# UWB_Project.net
KiCad netlist of a schematic drawn in Altium Designer
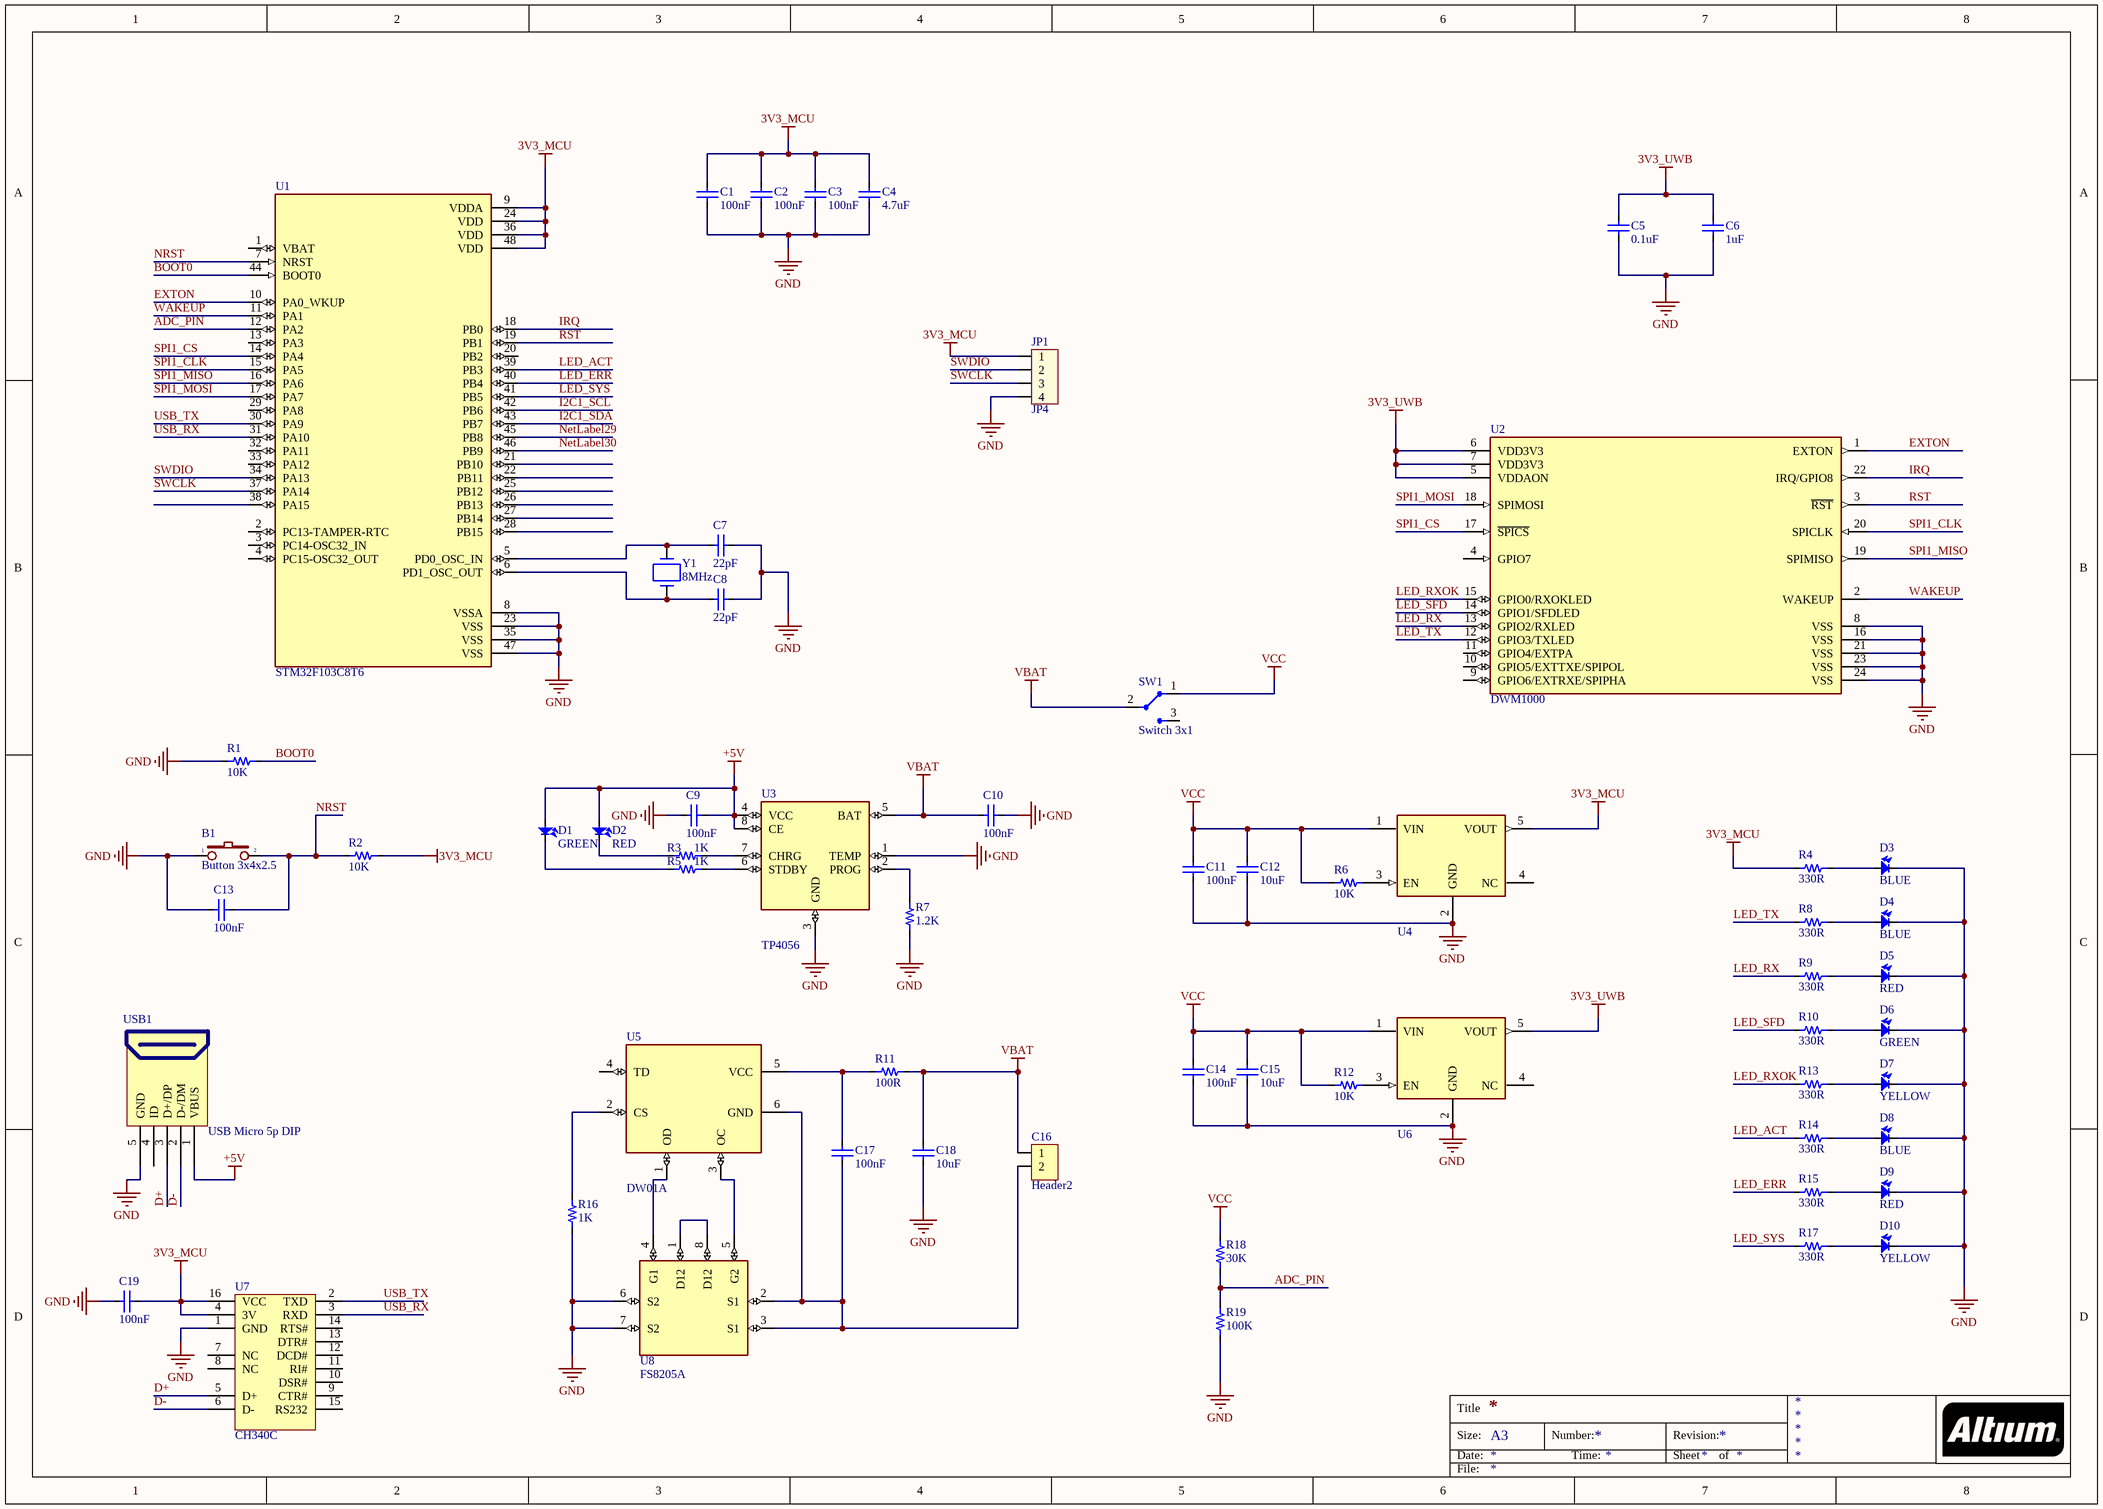
[diagram p0: UWB_Project.SchDoc]

(export (version "E")
  (design (tool "Eeschema 10.0.6"))
  (components
    (comp (ref "B1")
      (value "Button 3x4x2.5")
      (footprint "Button 3x4x2.5")
      (libsource (lib "Dung Library") (part "Button 3x4x2.5"))
    )
    (comp (ref "C1")
      (value "100nF")
      (footprint "CAP_0805")
      (description "Capacitor")
      (fields (field (name "PUBLISHER") "Altium Limited"))
      (libsource (lib "bla") (part "CapSMD"))
    )
    (comp (ref "C2")
      (value "100nF")
      (footprint "CAP_0805")
      (description "Capacitor")
      (fields (field (name "PUBLISHER") "Altium Limited"))
      (libsource (lib "bla") (part "CapSMD"))
    )
    (comp (ref "C3")
      (value "100nF")
      (footprint "CAP_0805")
      (description "Capacitor")
      (fields (field (name "PUBLISHER") "Altium Limited"))
      (libsource (lib "bla") (part "CapSMD"))
    )
    (comp (ref "C4")
      (value "4.7uF")
      (footprint "CAP_0805")
      (description "Capacitor")
      (fields (field (name "PUBLISHER") "Altium Limited"))
      (libsource (lib "bla") (part "CapSMD"))
    )
    (comp (ref "C5")
      (value "0.1uF")
      (footprint "CAP_0805")
      (description "Capacitor")
      (fields (field (name "PUBLISHER") "Altium Limited"))
      (libsource (lib "bla") (part "CapSMD"))
    )
    (comp (ref "C6")
      (value "1uF")
      (footprint "CAP_0805")
      (description "Capacitor")
      (fields (field (name "PUBLISHER") "Altium Limited"))
      (libsource (lib "bla") (part "CapSMD"))
    )
    (comp (ref "C7")
      (value "22pF")
      (footprint "CAP_0805")
      (description "Capacitor")
      (fields (field (name "PUBLISHER") "Altium Limited"))
      (libsource (lib "bla") (part "CapSMD"))
    )
    (comp (ref "C8")
      (value "22pF")
      (footprint "CAP_0805")
      (description "Capacitor")
      (fields (field (name "PUBLISHER") "Altium Limited"))
      (libsource (lib "bla") (part "CapSMD"))
    )
    (comp (ref "C9")
      (value "100nF")
      (footprint "CAP_0805")
      (description "Capacitor")
      (fields (field (name "PUBLISHER") "Altium Limited"))
      (libsource (lib "bla") (part "CapSMD"))
    )
    (comp (ref "C10")
      (value "100nF")
      (footprint "CAP_0805")
      (description "Capacitor")
      (fields (field (name "PUBLISHER") "Altium Limited"))
      (libsource (lib "bla") (part "CapSMD"))
    )
    (comp (ref "C11")
      (value "100nF")
      (footprint "CAP_0805")
      (description "Capacitor")
      (fields (field (name "PUBLISHER") "Altium Limited"))
      (libsource (lib "bla") (part "CapSMD"))
    )
    (comp (ref "C12")
      (value "10uF")
      (footprint "CAP_0805")
      (description "Capacitor")
      (fields (field (name "PUBLISHER") "Altium Limited"))
      (libsource (lib "bla") (part "CapSMD"))
    )
    (comp (ref "C13")
      (value "100nF")
      (footprint "CAP_0805")
      (description "Capacitor")
      (fields (field (name "PUBLISHER") "Altium Limited"))
      (libsource (lib "bla") (part "CapSMD"))
    )
    (comp (ref "C14")
      (value "100nF")
      (footprint "CAP_0805")
      (description "Capacitor")
      (fields (field (name "PUBLISHER") "Altium Limited"))
      (libsource (lib "bla") (part "CapSMD"))
    )
    (comp (ref "C15")
      (value "10uF")
      (footprint "CAP_0805")
      (description "Capacitor")
      (fields (field (name "PUBLISHER") "Altium Limited"))
      (libsource (lib "bla") (part "CapSMD"))
    )
    (comp (ref "C16")
      (value "Header2")
      (footprint "HEAD2P-1.25")
      (description "Header IDC, 2 x 1 Pin Vertical 2.54mm Pitch (Non-Boxed, Male)")
      (fields
        (field (name "MANUFACTURER") "Würth Elektronik eiSos GmbH")
        (field (name "PARTNO") "613002143121")
        (field (name "CREATED BY") "Karrer Zheng")
      )
      (libsource (lib "bla") (part "Header2"))
    )
    (comp (ref "C17")
      (value "100nF")
      (footprint "CAP_0805")
      (description "Capacitor")
      (fields (field (name "PUBLISHER") "Altium Limited"))
      (libsource (lib "bla") (part "CapSMD"))
    )
    (comp (ref "C18")
      (value "10uF")
      (footprint "CAP_0805")
      (description "Capacitor")
      (fields (field (name "PUBLISHER") "Altium Limited"))
      (libsource (lib "bla") (part "CapSMD"))
    )
    (comp (ref "C19")
      (value "100nF")
      (footprint "CAP_0805")
      (description "Capacitor")
      (fields (field (name "PUBLISHER") "Altium Limited"))
      (libsource (lib "bla") (part "CapSMD"))
    )
    (comp (ref "D1")
      (value "GREEN")
      (footprint "LED-0805-Green")
      (description "LED Single colour Green and Red")
      (libsource (lib "bla") (part "LED"))
    )
    (comp (ref "D2")
      (value "RED")
      (footprint "LED-0805-Red")
      (description "LED Single colour Green and Red")
      (libsource (lib "bla") (part "LED"))
    )
    (comp (ref "D3")
      (value "BLUE")
      (footprint "LED-0805-Blue")
      (description "LED Single colour Green and Red")
      (libsource (lib "bla") (part "LED"))
    )
    (comp (ref "D4")
      (value "BLUE")
      (footprint "LED-0805-Red")
      (description "LED Single colour Green and Red")
      (libsource (lib "bla") (part "LED"))
    )
    (comp (ref "D5")
      (value "RED")
      (footprint "LED-0805-Green")
      (description "LED Single colour Green and Red")
      (libsource (lib "bla") (part "LED"))
    )
    (comp (ref "D6")
      (value "GREEN")
      (footprint "LED-0805-Yellow")
      (description "LED Single colour Green and Red")
      (libsource (lib "bla") (part "LED"))
    )
    (comp (ref "D7")
      (value "YELLOW")
      (footprint "LED-0805-Yellow")
      (description "LED Single colour Green and Red")
      (libsource (lib "bla") (part "LED"))
    )
    (comp (ref "D8")
      (value "BLUE")
      (footprint "LED-0805-Yellow")
      (description "LED Single colour Green and Red")
      (libsource (lib "bla") (part "LED"))
    )
    (comp (ref "D9")
      (value "RED")
      (footprint "LED-0805-Yellow")
      (description "LED Single colour Green and Red")
      (libsource (lib "bla") (part "LED"))
    )
    (comp (ref "D10")
      (value "YELLOW")
      (footprint "LED-0805-Yellow")
      (description "LED Single colour Green and Red")
      (libsource (lib "bla") (part "LED"))
    )
    (comp (ref "JP1")
      (value "JP4")
      (footprint "HEADER4P-1.25")
      (description "Connector 4")
      (libsource (lib "bla") (part "Con4"))
    )
    (comp (ref "R1")
      (value "10K")
      (footprint "RES-SMD-0805")
      (description "Resistor")
      (fields
        (field (name "MANUFACTURER") "Generic Components")
        (field (name "PUBLISHER") "Altium Hobart Technology Centre")
      )
      (libsource (lib "bla") (part "Resistor - SMD"))
    )
    (comp (ref "R2")
      (value "10K")
      (footprint "RES-SMD-0805")
      (description "Resistor")
      (fields
        (field (name "MANUFACTURER") "Generic Components")
        (field (name "PUBLISHER") "Altium Hobart Technology Centre")
      )
      (libsource (lib "bla") (part "Resistor - SMD"))
    )
    (comp (ref "R3")
      (value "1K")
      (footprint "RES-SMD-0805")
      (description "Resistor")
      (fields
        (field (name "MANUFACTURER") "Generic Components")
        (field (name "PUBLISHER") "Altium Hobart Technology Centre")
      )
      (libsource (lib "bla") (part "Resistor - SMD"))
    )
    (comp (ref "R4")
      (value "330R")
      (footprint "RES-SMD-0805")
      (description "Resistor")
      (fields
        (field (name "MANUFACTURER") "Generic Components")
        (field (name "PUBLISHER") "Altium Hobart Technology Centre")
      )
      (libsource (lib "bla") (part "Resistor - SMD"))
    )
    (comp (ref "R5")
      (value "1K")
      (footprint "RES-SMD-0805")
      (description "Resistor")
      (fields
        (field (name "MANUFACTURER") "Generic Components")
        (field (name "PUBLISHER") "Altium Hobart Technology Centre")
      )
      (libsource (lib "bla") (part "Resistor - SMD"))
    )
    (comp (ref "R6")
      (value "10K")
      (footprint "RES-SMD-0805")
      (description "Resistor")
      (fields
        (field (name "MANUFACTURER") "Generic Components")
        (field (name "PUBLISHER") "Altium Hobart Technology Centre")
      )
      (libsource (lib "bla") (part "Resistor - SMD"))
    )
    (comp (ref "R7")
      (value "1.2K")
      (footprint "RES-SMD-0805")
      (description "Resistor")
      (fields
        (field (name "MANUFACTURER") "Generic Components")
        (field (name "PUBLISHER") "Altium Hobart Technology Centre")
      )
      (libsource (lib "bla") (part "Resistor - SMD"))
    )
    (comp (ref "R8")
      (value "330R")
      (footprint "RES-SMD-0805")
      (description "Resistor")
      (fields
        (field (name "MANUFACTURER") "Generic Components")
        (field (name "PUBLISHER") "Altium Hobart Technology Centre")
      )
      (libsource (lib "bla") (part "Resistor - SMD"))
    )
    (comp (ref "R9")
      (value "330R")
      (footprint "RES-SMD-0805")
      (description "Resistor")
      (fields
        (field (name "MANUFACTURER") "Generic Components")
        (field (name "PUBLISHER") "Altium Hobart Technology Centre")
      )
      (libsource (lib "bla") (part "Resistor - SMD"))
    )
    (comp (ref "R10")
      (value "330R")
      (footprint "RES-SMD-0805")
      (description "Resistor")
      (fields
        (field (name "MANUFACTURER") "Generic Components")
        (field (name "PUBLISHER") "Altium Hobart Technology Centre")
      )
      (libsource (lib "bla") (part "Resistor - SMD"))
    )
    (comp (ref "R11")
      (value "100R")
      (footprint "RES-SMD-0805")
      (description "Resistor")
      (fields
        (field (name "MANUFACTURER") "Generic Components")
        (field (name "PUBLISHER") "Altium Hobart Technology Centre")
      )
      (libsource (lib "bla") (part "Resistor - SMD"))
    )
    (comp (ref "R12")
      (value "10K")
      (footprint "RES-SMD-0805")
      (description "Resistor")
      (fields
        (field (name "MANUFACTURER") "Generic Components")
        (field (name "PUBLISHER") "Altium Hobart Technology Centre")
      )
      (libsource (lib "bla") (part "Resistor - SMD"))
    )
    (comp (ref "R13")
      (value "330R")
      (footprint "RES-SMD-0805")
      (description "Resistor")
      (fields
        (field (name "MANUFACTURER") "Generic Components")
        (field (name "PUBLISHER") "Altium Hobart Technology Centre")
      )
      (libsource (lib "bla") (part "Resistor - SMD"))
    )
    (comp (ref "R14")
      (value "330R")
      (footprint "RES-SMD-0805")
      (description "Resistor")
      (fields
        (field (name "MANUFACTURER") "Generic Components")
        (field (name "PUBLISHER") "Altium Hobart Technology Centre")
      )
      (libsource (lib "bla") (part "Resistor - SMD"))
    )
    (comp (ref "R15")
      (value "330R")
      (footprint "RES-SMD-0805")
      (description "Resistor")
      (fields
        (field (name "MANUFACTURER") "Generic Components")
        (field (name "PUBLISHER") "Altium Hobart Technology Centre")
      )
      (libsource (lib "bla") (part "Resistor - SMD"))
    )
    (comp (ref "R16")
      (value "1K")
      (footprint "RES-SMD-0805")
      (description "Resistor")
      (fields
        (field (name "MANUFACTURER") "Generic Components")
        (field (name "PUBLISHER") "Altium Hobart Technology Centre")
      )
      (libsource (lib "bla") (part "Resistor - SMD"))
    )
    (comp (ref "R17")
      (value "330R")
      (footprint "RES-SMD-0805")
      (description "Resistor")
      (fields
        (field (name "MANUFACTURER") "Generic Components")
        (field (name "PUBLISHER") "Altium Hobart Technology Centre")
      )
      (libsource (lib "bla") (part "Resistor - SMD"))
    )
    (comp (ref "R18")
      (value "30K")
      (footprint "RES-SMD-0805")
      (description "Resistor")
      (fields
        (field (name "MANUFACTURER") "Generic Components")
        (field (name "PUBLISHER") "Altium Hobart Technology Centre")
      )
      (libsource (lib "bla") (part "Resistor - SMD"))
    )
    (comp (ref "R19")
      (value "100K")
      (footprint "RES-SMD-0805")
      (description "Resistor")
      (fields
        (field (name "MANUFACTURER") "Generic Components")
        (field (name "PUBLISHER") "Altium Hobart Technology Centre")
      )
      (libsource (lib "bla") (part "Resistor - SMD"))
    )
    (comp (ref "SW1") (value "Switch 3x1") (footprint "SLIDE_SW") (libsource (lib "bla") (part "SW3x1")))
    (comp (ref "U1")
      (value "STM32F103C8T6")
      (footprint "STM32F103C8T6")
      (libsource (lib "bla") (part "STM32F103C8T6"))
    )
    (comp (ref "U2")
      (value "DWM1000")
      (footprint "DW1000")
      (description "Decawave's DW1000 Ultra\r\nWideband (UWB) transceiver IC")
      (libsource (lib "bla") (part "DWM1000"))
    )
    (comp (ref "U3")
      (value "TP4056")
      (footprint "TP4056")
      (description "Complete single cell Li-Ion battery with a constant current / constant voltage linear charger")
      (libsource (lib "bla") (part "TP4056"))
    )
    (comp (ref "U4") (value "RT9013") (footprint "RT9013") (libsource (lib "bla") (part "RT9013")))
    (comp (ref "U5")
      (value "DW01A")
      (footprint "SOT23-6")
      (description "One Cell Lithium-ion/Polymer Battery Protection IC")
      (libsource (lib "bla") (part "DW01A"))
    )
    (comp (ref "U6") (value "RT9013") (footprint "RT9013") (libsource (lib "bla") (part "RT9013")))
    (comp (ref "U7") (value "CH340C") (footprint "SO16") (libsource (lib "bla") (part "CH340C")))
    (comp (ref "U8") (value "FS8205A") (footprint "FS8205A") (libsource (lib "bla") (part "FS8205A")))
    (comp (ref "USB1")
      (value "USB Micro 5p DIP")
      (footprint "USB Micro 5p DIP")
      (description "USB Type B")
      (libsource (lib "Altium_Lib_by_KhueNguyenCreator") (part "USB Micro 5p DIP"))
    )
    (comp (ref "Y1")
      (value "8MHz")
      (footprint "ABM7_v1_1_BIG")
      (description "CRYSTAL 16MHZ 18PF SMD")
      (fields
        (field (name "MANUFACTURER") "Abracon LLC")
        (field (name "MANUFACTURER PART NUMBER") "ABM7-16.000MHZ-D2Y-T")
        (field (name ".CREATOR") "MM")
        (field (name ".CHECKED PCB") "RF")
        (field (name ".CHECKED SCH") "RF")
      )
      (libsource (lib "GPS_Traking_V1_1") (part "ABM7-16.000MHZ-D2Y-T"))
    )
  )
  (nets
    (net (code "1") (name "+5V") (class "Default")
      (node (ref "C9") (pin "2") (pinfunction "2_2") (pintype "passive"))
      (node (ref "D1") (pin "1") (pinfunction "1_1") (pintype "passive"))
      (node (ref "D2") (pin "1") (pinfunction "1_1") (pintype "passive"))
      (node (ref "U3") (pin "4") (pinfunction "VCC_4") (pintype "bidirectional"))
      (node (ref "U3") (pin "8") (pinfunction "CE_8") (pintype "bidirectional"))
      (node (ref "USB1") (pin "1") (pinfunction "VBUS_1") (pintype "passive"))
    )
    (net (code "2") (name "/ADC_PIN") (class "Default")
      (node (ref "R18") (pin "1") (pinfunction "1_1") (pintype "passive"))
      (node (ref "R19") (pin "2") (pinfunction "2_2") (pintype "passive"))
      (node (ref "U1") (pin "12") (pinfunction "PA2_12") (pintype "bidirectional"))
    )
    (net (code "3") (name "/BOOT0") (class "Default")
      (node (ref "R1") (pin "2") (pinfunction "2_2") (pintype "passive"))
      (node (ref "U1") (pin "44") (pinfunction "BOOT0_44") (pintype "input"))
    )
    (net (code "4") (name "/D+") (class "Default")
      (node (ref "U7") (pin "5") (pinfunction "D+_5") (pintype "passive"))
      (node (ref "USB1") (pin "3") (pinfunction "D+/DP_3") (pintype "passive"))
    )
    (net (code "5") (name "/D-") (class "Default")
      (node (ref "U7") (pin "6") (pinfunction "D-_6") (pintype "passive"))
      (node (ref "USB1") (pin "2") (pinfunction "D-/DM_2") (pintype "passive"))
    )
    (net (code "6") (name "/EXTON") (class "Default")
      (node (ref "U1") (pin "10") (pinfunction "PA0_WKUP_10") (pintype "bidirectional"))
      (node (ref "U2") (pin "1") (pinfunction "EXTON_1") (pintype "output"))
    )
    (net (code "7") (name "/I2C1_SCL") (class "Default")
      (node (ref "U1") (pin "42") (pinfunction "PB6_42") (pintype "bidirectional"))
    )
    (net (code "8") (name "/I2C1_SDA") (class "Default")
      (node (ref "U1") (pin "43") (pinfunction "PB7_43") (pintype "bidirectional"))
    )
    (net (code "9") (name "/IRQ") (class "Default")
      (node (ref "U1") (pin "18") (pinfunction "PB0_18") (pintype "bidirectional"))
      (node (ref "U2") (pin "22") (pinfunction "IRQ/GPIO8_22") (pintype "output"))
    )
    (net (code "10") (name "/LED_ACT") (class "Default")
      (node (ref "R14") (pin "1") (pinfunction "1_1") (pintype "passive"))
      (node (ref "U1") (pin "39") (pinfunction "PB3_39") (pintype "bidirectional"))
    )
    (net (code "11") (name "/LED_ERR") (class "Default")
      (node (ref "R15") (pin "1") (pinfunction "1_1") (pintype "passive"))
      (node (ref "U1") (pin "40") (pinfunction "PB4_40") (pintype "bidirectional"))
    )
    (net (code "12") (name "/LED_RX") (class "Default")
      (node (ref "R9") (pin "1") (pinfunction "1_1") (pintype "passive"))
      (node (ref "U2") (pin "13") (pinfunction "GPIO2/RXLED_13") (pintype "bidirectional"))
    )
    (net (code "13") (name "/LED_RXOK") (class "Default")
      (node (ref "R13") (pin "1") (pinfunction "1_1") (pintype "passive"))
      (node (ref "U2") (pin "15") (pinfunction "GPIO0/RXOKLED_15") (pintype "bidirectional"))
    )
    (net (code "14") (name "/LED_SFD") (class "Default")
      (node (ref "R10") (pin "1") (pinfunction "1_1") (pintype "passive"))
      (node (ref "U2") (pin "14") (pinfunction "GPIO1/SFDLED_14") (pintype "bidirectional"))
    )
    (net (code "15") (name "/LED_SYS") (class "Default")
      (node (ref "R17") (pin "1") (pinfunction "1_1") (pintype "passive"))
      (node (ref "U1") (pin "41") (pinfunction "PB5_41") (pintype "bidirectional"))
    )
    (net (code "16") (name "/LED_TX") (class "Default")
      (node (ref "R8") (pin "1") (pinfunction "1_1") (pintype "passive"))
      (node (ref "U2") (pin "12") (pinfunction "GPIO3/TXLED_12") (pintype "bidirectional"))
    )
    (net (code "17") (name "/NRST") (class "Default")
      (node (ref "B1") (pin "2") (pinfunction "2_2") (pintype "passive"))
      (node (ref "C13") (pin "2") (pinfunction "2_2") (pintype "passive"))
      (node (ref "R2") (pin "1") (pinfunction "1_1") (pintype "passive"))
      (node (ref "U1") (pin "7") (pinfunction "NRST_7") (pintype "input"))
    )
    (net (code "18") (name "/NetLabel29") (class "Default")
      (node (ref "U1") (pin "45") (pinfunction "PB8_45") (pintype "bidirectional"))
    )
    (net (code "19") (name "/NetLabel30") (class "Default")
      (node (ref "U1") (pin "46") (pinfunction "PB9_46") (pintype "bidirectional"))
    )
    (net (code "20") (name "/RST") (class "Default")
      (node (ref "U1") (pin "19") (pinfunction "PB1_19") (pintype "bidirectional"))
      (node (ref "U2") (pin "3") (pinfunction "~{RST}_3") (pintype "output"))
    )
    (net (code "21") (name "/SPI1_CLK") (class "Default")
      (node (ref "U1") (pin "15") (pinfunction "PA5_15") (pintype "bidirectional"))
      (node (ref "U2") (pin "20") (pinfunction "SPICLK_20") (pintype "input"))
    )
    (net (code "22") (name "/SPI1_CS") (class "Default")
      (node (ref "U1") (pin "14") (pinfunction "PA4_14") (pintype "bidirectional"))
      (node (ref "U2") (pin "17") (pinfunction "~{SPICS}_17") (pintype "input"))
    )
    (net (code "23") (name "/SPI1_MISO") (class "Default")
      (node (ref "U1") (pin "16") (pinfunction "PA6_16") (pintype "bidirectional"))
      (node (ref "U2") (pin "19") (pinfunction "SPIMISO_19") (pintype "output"))
    )
    (net (code "24") (name "/SPI1_MOSI") (class "Default")
      (node (ref "U1") (pin "17") (pinfunction "PA7_17") (pintype "bidirectional"))
      (node (ref "U2") (pin "18") (pinfunction "SPIMOSI_18") (pintype "input"))
    )
    (net (code "25") (name "/SWCLK") (class "Default")
      (node (ref "JP1") (pin "3") (pinfunction "3_3") (pintype "passive"))
      (node (ref "U1") (pin "37") (pinfunction "PA14_37") (pintype "bidirectional"))
    )
    (net (code "26") (name "/SWDIO") (class "Default")
      (node (ref "JP1") (pin "2") (pinfunction "2_2") (pintype "passive"))
      (node (ref "U1") (pin "34") (pinfunction "PA13_34") (pintype "bidirectional"))
    )
    (net (code "27") (name "/USB_RX") (class "Default")
      (node (ref "U1") (pin "31") (pinfunction "PA10_31") (pintype "bidirectional"))
      (node (ref "U7") (pin "3") (pinfunction "RXD_3") (pintype "passive"))
    )
    (net (code "28") (name "/USB_TX") (class "Default")
      (node (ref "U1") (pin "30") (pinfunction "PA9_30") (pintype "bidirectional"))
      (node (ref "U7") (pin "2") (pinfunction "TXD_2") (pintype "passive"))
    )
    (net (code "29") (name "/WAKEUP") (class "Default")
      (node (ref "U1") (pin "11") (pinfunction "PA1_11") (pintype "bidirectional"))
      (node (ref "U2") (pin "2") (pinfunction "WAKEUP_2") (pintype "passive"))
    )
    (net (code "30") (name "3V3_MCU") (class "Default")
      (node (ref "C1") (pin "2") (pinfunction "2_2") (pintype "passive"))
      (node (ref "C19") (pin "2") (pinfunction "2_2") (pintype "passive"))
      (node (ref "C2") (pin "2") (pinfunction "2_2") (pintype "passive"))
      (node (ref "C3") (pin "2") (pinfunction "2_2") (pintype "passive"))
      (node (ref "C4") (pin "2") (pinfunction "2_2") (pintype "passive"))
      (node (ref "JP1") (pin "1") (pinfunction "1_1") (pintype "passive"))
      (node (ref "R2") (pin "2") (pinfunction "2_2") (pintype "passive"))
      (node (ref "R4") (pin "1") (pinfunction "1_1") (pintype "passive"))
      (node (ref "U1") (pin "24") (pinfunction "VDD_24") (pintype "power_in"))
      (node (ref "U1") (pin "36") (pinfunction "VDD_36") (pintype "power_in"))
      (node (ref "U1") (pin "48") (pinfunction "VDD_48") (pintype "power_in"))
      (node (ref "U1") (pin "9") (pinfunction "VDDA_9") (pintype "power_in"))
      (node (ref "U4") (pin "5") (pinfunction "VOUT_5") (pintype "output"))
      (node (ref "U7") (pin "16") (pinfunction "VCC_16") (pintype "passive"))
      (node (ref "U7") (pin "4") (pinfunction "3V_4") (pintype "passive"))
    )
    (net (code "31") (name "3V3_UWB") (class "Default")
      (node (ref "C5") (pin "2") (pinfunction "2_2") (pintype "passive"))
      (node (ref "C6") (pin "2") (pinfunction "2_2") (pintype "passive"))
      (node (ref "U2") (pin "5") (pinfunction "VDDAON_5") (pintype "power_in"))
      (node (ref "U2") (pin "6") (pinfunction "VDD3V3_6") (pintype "power_in"))
      (node (ref "U2") (pin "7") (pinfunction "VDD3V3_7") (pintype "power_in"))
      (node (ref "U6") (pin "5") (pinfunction "VOUT_5") (pintype "output"))
    )
    (net (code "32") (name "GND") (class "Default")
      (node (ref "B1") (pin "1") (pinfunction "1_1") (pintype "passive"))
      (node (ref "C1") (pin "1") (pinfunction "1_1") (pintype "passive"))
      (node (ref "C10") (pin "2") (pinfunction "2_2") (pintype "passive"))
      (node (ref "C11") (pin "1") (pinfunction "1_1") (pintype "passive"))
      (node (ref "C12") (pin "1") (pinfunction "1_1") (pintype "passive"))
      (node (ref "C13") (pin "1") (pinfunction "1_1") (pintype "passive"))
      (node (ref "C14") (pin "1") (pinfunction "1_1") (pintype "passive"))
      (node (ref "C15") (pin "1") (pinfunction "1_1") (pintype "passive"))
      (node (ref "C18") (pin "1") (pinfunction "1_1") (pintype "passive"))
      (node (ref "C19") (pin "1") (pinfunction "1_1") (pintype "passive"))
      (node (ref "C2") (pin "1") (pinfunction "1_1") (pintype "passive"))
      (node (ref "C3") (pin "1") (pinfunction "1_1") (pintype "passive"))
      (node (ref "C4") (pin "1") (pinfunction "1_1") (pintype "passive"))
      (node (ref "C5") (pin "1") (pinfunction "1_1") (pintype "passive"))
      (node (ref "C6") (pin "1") (pinfunction "1_1") (pintype "passive"))
      (node (ref "C7") (pin "2") (pinfunction "2_2") (pintype "passive"))
      (node (ref "C8") (pin "2") (pinfunction "2_2") (pintype "passive"))
      (node (ref "C9") (pin "1") (pinfunction "1_1") (pintype "passive"))
      (node (ref "D10") (pin "2") (pinfunction "2_2") (pintype "passive"))
      (node (ref "D3") (pin "2") (pinfunction "2_2") (pintype "passive"))
      (node (ref "D4") (pin "2") (pinfunction "2_2") (pintype "passive"))
      (node (ref "D5") (pin "2") (pinfunction "2_2") (pintype "passive"))
      (node (ref "D6") (pin "2") (pinfunction "2_2") (pintype "passive"))
      (node (ref "D7") (pin "2") (pinfunction "2_2") (pintype "passive"))
      (node (ref "D8") (pin "2") (pinfunction "2_2") (pintype "passive"))
      (node (ref "D9") (pin "2") (pinfunction "2_2") (pintype "passive"))
      (node (ref "JP1") (pin "4") (pinfunction "4_4") (pintype "passive"))
      (node (ref "R1") (pin "1") (pinfunction "1_1") (pintype "passive"))
      (node (ref "R16") (pin "1") (pinfunction "1_1") (pintype "passive"))
      (node (ref "R19") (pin "1") (pinfunction "1_1") (pintype "passive"))
      (node (ref "R7") (pin "1") (pinfunction "1_1") (pintype "passive"))
      (node (ref "U1") (pin "23") (pinfunction "VSS_23") (pintype "power_in"))
      (node (ref "U1") (pin "35") (pinfunction "VSS_35") (pintype "power_in"))
      (node (ref "U1") (pin "47") (pinfunction "VSS_47") (pintype "power_in"))
      (node (ref "U1") (pin "8") (pinfunction "VSSA_8") (pintype "power_in"))
      (node (ref "U2") (pin "16") (pinfunction "VSS_16") (pintype "power_in"))
      (node (ref "U2") (pin "21") (pinfunction "VSS_21") (pintype "power_in"))
      (node (ref "U2") (pin "23") (pinfunction "VSS_23") (pintype "power_in"))
      (node (ref "U2") (pin "24") (pinfunction "VSS_24") (pintype "power_in"))
      (node (ref "U2") (pin "8") (pinfunction "VSS_8") (pintype "power_in"))
      (node (ref "U3") (pin "1") (pinfunction "TEMP_1") (pintype "bidirectional"))
      (node (ref "U3") (pin "3") (pinfunction "GND_3") (pintype "bidirectional"))
      (node (ref "U4") (pin "2") (pinfunction "GND_2") (pintype "power_in"))
      (node (ref "U6") (pin "2") (pinfunction "GND_2") (pintype "power_in"))
      (node (ref "U7") (pin "1") (pinfunction "GND_1") (pintype "passive"))
      (node (ref "U8") (pin "6") (pinfunction "S2_6") (pintype "bidirectional"))
      (node (ref "U8") (pin "7") (pinfunction "S2_7") (pintype "bidirectional"))
      (node (ref "USB1") (pin "5") (pinfunction "GND_5") (pintype "passive"))
    )
    (net (code "33") (name "Net-(D1-Pad2)") (class "Default")
      (node (ref "D1") (pin "2") (pinfunction "2_2") (pintype "passive"))
      (node (ref "R5") (pin "1") (pinfunction "1_1") (pintype "passive"))
    )
    (net (code "34") (name "Net-(D2-Pad2)") (class "Default")
      (node (ref "D2") (pin "2") (pinfunction "2_2") (pintype "passive"))
      (node (ref "R3") (pin "1") (pinfunction "1_1") (pintype "passive"))
    )
    (net (code "35") (name "Net-(D3-Pad1)") (class "Default")
      (node (ref "D3") (pin "1") (pinfunction "1_1") (pintype "passive"))
      (node (ref "R4") (pin "2") (pinfunction "2_2") (pintype "passive"))
    )
    (net (code "36") (name "Net-(D4-Pad1)") (class "Default")
      (node (ref "D4") (pin "1") (pinfunction "1_1") (pintype "passive"))
      (node (ref "R8") (pin "2") (pinfunction "2_2") (pintype "passive"))
    )
    (net (code "37") (name "Net-(D5-Pad1)") (class "Default")
      (node (ref "D5") (pin "1") (pinfunction "1_1") (pintype "passive"))
      (node (ref "R9") (pin "2") (pinfunction "2_2") (pintype "passive"))
    )
    (net (code "38") (name "Net-(D6-Pad1)") (class "Default")
      (node (ref "D6") (pin "1") (pinfunction "1_1") (pintype "passive"))
      (node (ref "R10") (pin "2") (pinfunction "2_2") (pintype "passive"))
    )
    (net (code "39") (name "Net-(D7-Pad1)") (class "Default")
      (node (ref "D7") (pin "1") (pinfunction "1_1") (pintype "passive"))
      (node (ref "R13") (pin "2") (pinfunction "2_2") (pintype "passive"))
    )
    (net (code "40") (name "Net-(D8-Pad1)") (class "Default")
      (node (ref "D8") (pin "1") (pinfunction "1_1") (pintype "passive"))
      (node (ref "R14") (pin "2") (pinfunction "2_2") (pintype "passive"))
    )
    (net (code "41") (name "Net-(D9-Pad1)") (class "Default")
      (node (ref "D9") (pin "1") (pinfunction "1_1") (pintype "passive"))
      (node (ref "R15") (pin "2") (pinfunction "2_2") (pintype "passive"))
    )
    (net (code "42") (name "Net-(D10-Pad1)") (class "Default")
      (node (ref "D10") (pin "1") (pinfunction "1_1") (pintype "passive"))
      (node (ref "R17") (pin "2") (pinfunction "2_2") (pintype "passive"))
    )
    (net (code "43") (name "Net-(U1-PD0_OSC_IN)") (class "Default")
      (node (ref "C7") (pin "1") (pinfunction "1_1") (pintype "passive"))
      (node (ref "U1") (pin "5") (pinfunction "PD0_OSC_IN_5") (pintype "bidirectional"))
      (node (ref "Y1") (pin "2") (pinfunction "2_2") (pintype "passive"))
    )
    (net (code "44") (name "Net-(U1-PD1_OSC_OUT)") (class "Default")
      (node (ref "C8") (pin "1") (pinfunction "1_1") (pintype "passive"))
      (node (ref "U1") (pin "6") (pinfunction "PD1_OSC_OUT_6") (pintype "bidirectional"))
      (node (ref "Y1") (pin "1") (pinfunction "1_1") (pintype "passive"))
    )
    (net (code "45") (name "Net-(U3-CHRG)") (class "Default")
      (node (ref "R3") (pin "2") (pinfunction "2_2") (pintype "passive"))
      (node (ref "U3") (pin "7") (pinfunction "CHRG_7") (pintype "bidirectional"))
    )
    (net (code "46") (name "Net-(U3-PROG)") (class "Default")
      (node (ref "R7") (pin "2") (pinfunction "2_2") (pintype "passive"))
      (node (ref "U3") (pin "2") (pinfunction "PROG_2") (pintype "bidirectional"))
    )
    (net (code "47") (name "Net-(U3-STDBY)") (class "Default")
      (node (ref "R5") (pin "2") (pinfunction "2_2") (pintype "passive"))
      (node (ref "U3") (pin "6") (pinfunction "STDBY_6") (pintype "bidirectional"))
    )
    (net (code "48") (name "Net-(U4-EN)") (class "Default")
      (node (ref "R6") (pin "1") (pinfunction "1_1") (pintype "passive"))
      (node (ref "U4") (pin "3") (pinfunction "EN_3") (pintype "input"))
    )
    (net (code "49") (name "Net-(U5-CS)") (class "Default")
      (node (ref "R16") (pin "2") (pinfunction "2_2") (pintype "passive"))
      (node (ref "U5") (pin "2") (pinfunction "CS_2") (pintype "bidirectional"))
    )
    (net (code "50") (name "Net-(U5-GND)") (class "Default")
      (node (ref "C16") (pin "2") (pinfunction "2_2") (pintype "passive"))
      (node (ref "C17") (pin "1") (pinfunction "1_1") (pintype "passive"))
      (node (ref "U5") (pin "6") (pinfunction "GND_6") (pintype "power_in"))
      (node (ref "U8") (pin "2") (pinfunction "S1_2") (pintype "bidirectional"))
      (node (ref "U8") (pin "3") (pinfunction "S1_3") (pintype "bidirectional"))
    )
    (net (code "51") (name "Net-(U5-OC)") (class "Default")
      (node (ref "U5") (pin "3") (pinfunction "OC_3") (pintype "bidirectional"))
      (node (ref "U8") (pin "5") (pinfunction "G2_5") (pintype "bidirectional"))
    )
    (net (code "52") (name "Net-(U5-OD)") (class "Default")
      (node (ref "U5") (pin "1") (pinfunction "OD_1") (pintype "bidirectional"))
      (node (ref "U8") (pin "4") (pinfunction "G1_4") (pintype "bidirectional"))
    )
    (net (code "53") (name "Net-(U5-VCC)") (class "Default")
      (node (ref "C17") (pin "2") (pinfunction "2_2") (pintype "passive"))
      (node (ref "R11") (pin "1") (pinfunction "1_1") (pintype "passive"))
      (node (ref "U5") (pin "5") (pinfunction "VCC_5") (pintype "power_in"))
    )
    (net (code "54") (name "Net-(U6-EN)") (class "Default")
      (node (ref "R12") (pin "1") (pinfunction "1_1") (pintype "passive"))
      (node (ref "U6") (pin "3") (pinfunction "EN_3") (pintype "input"))
    )
    (net (code "55") (name "Net-(U8-D12-Pad1)") (class "Default")
      (node (ref "U8") (pin "1") (pinfunction "D12_1") (pintype "bidirectional"))
      (node (ref "U8") (pin "8") (pinfunction "D12_8") (pintype "bidirectional"))
    )
    (net (code "56") (name "VBAT") (class "Default")
      (node (ref "C10") (pin "1") (pinfunction "1_1") (pintype "passive"))
      (node (ref "C16") (pin "1") (pinfunction "1_1") (pintype "passive"))
      (node (ref "C18") (pin "2") (pinfunction "2_2") (pintype "passive"))
      (node (ref "R11") (pin "2") (pinfunction "2_2") (pintype "passive"))
      (node (ref "SW1") (pin "2") (pintype "passive"))
      (node (ref "U3") (pin "5") (pinfunction "BAT_5") (pintype "bidirectional"))
    )
    (net (code "57") (name "VCC") (class "Default")
      (node (ref "C11") (pin "2") (pinfunction "2_2") (pintype "passive"))
      (node (ref "C12") (pin "2") (pinfunction "2_2") (pintype "passive"))
      (node (ref "C14") (pin "2") (pinfunction "2_2") (pintype "passive"))
      (node (ref "C15") (pin "2") (pinfunction "2_2") (pintype "passive"))
      (node (ref "R12") (pin "2") (pinfunction "2_2") (pintype "passive"))
      (node (ref "R18") (pin "2") (pinfunction "2_2") (pintype "passive"))
      (node (ref "R6") (pin "2") (pinfunction "2_2") (pintype "passive"))
      (node (ref "SW1") (pin "1") (pintype "passive"))
      (node (ref "U4") (pin "1") (pinfunction "VIN_1") (pintype "power_in"))
      (node (ref "U6") (pin "1") (pinfunction "VIN_1") (pintype "power_in"))
    )
    (net (code "58") (name "unconnected-(SW1-I{slash}O2-Pad3)") (class "Default")
      (node (ref "SW1") (pin "3") (pinfunction "I/O2_3") (pintype "passive"))
    )
    (net (code "59") (name "unconnected-(U1-PA3-Pad13)") (class "Default")
      (node (ref "U1") (pin "13") (pinfunction "PA3_13") (pintype "bidirectional"))
    )
    (net (code "60") (name "unconnected-(U1-PA8-Pad29)") (class "Default")
      (node (ref "U1") (pin "29") (pinfunction "PA8_29") (pintype "bidirectional"))
    )
    (net (code "61") (name "unconnected-(U1-PA11-Pad32)") (class "Default")
      (node (ref "U1") (pin "32") (pinfunction "PA11_32") (pintype "bidirectional"))
    )
    (net (code "62") (name "unconnected-(U1-PA12-Pad33)") (class "Default")
      (node (ref "U1") (pin "33") (pinfunction "PA12_33") (pintype "bidirectional"))
    )
    (net (code "63") (name "unconnected-(U1-PA15-Pad38)") (class "Default")
      (node (ref "U1") (pin "38") (pinfunction "PA15_38") (pintype "bidirectional"))
    )
    (net (code "64") (name "unconnected-(U1-PB2-Pad20)") (class "Default")
      (node (ref "U1") (pin "20") (pinfunction "PB2_20") (pintype "bidirectional"))
    )
    (net (code "65") (name "unconnected-(U1-PB10-Pad21)") (class "Default")
      (node (ref "U1") (pin "21") (pinfunction "PB10_21") (pintype "bidirectional"))
    )
    (net (code "66") (name "unconnected-(U1-PB11-Pad22)") (class "Default")
      (node (ref "U1") (pin "22") (pinfunction "PB11_22") (pintype "bidirectional"))
    )
    (net (code "67") (name "unconnected-(U1-PB12-Pad25)") (class "Default")
      (node (ref "U1") (pin "25") (pinfunction "PB12_25") (pintype "bidirectional"))
    )
    (net (code "68") (name "unconnected-(U1-PB13-Pad26)") (class "Default")
      (node (ref "U1") (pin "26") (pinfunction "PB13_26") (pintype "bidirectional"))
    )
    (net (code "69") (name "unconnected-(U1-PB14-Pad27)") (class "Default")
      (node (ref "U1") (pin "27") (pinfunction "PB14_27") (pintype "bidirectional"))
    )
    (net (code "70") (name "unconnected-(U1-PB15-Pad28)") (class "Default")
      (node (ref "U1") (pin "28") (pinfunction "PB15_28") (pintype "bidirectional"))
    )
    (net (code "71") (name "unconnected-(U1-PC13-TAMPER-RTC-Pad2)") (class "Default")
      (node (ref "U1") (pin "2") (pinfunction "PC13-TAMPER-RTC_2") (pintype "bidirectional"))
    )
    (net (code "72") (name "unconnected-(U1-PC14-OSC32_IN-Pad3)") (class "Default")
      (node (ref "U1") (pin "3") (pinfunction "PC14-OSC32_IN_3") (pintype "bidirectional"))
    )
    (net (code "73") (name "unconnected-(U1-PC15-OSC32_OUT-Pad4)") (class "Default")
      (node (ref "U1") (pin "4") (pinfunction "PC15-OSC32_OUT_4") (pintype "bidirectional"))
    )
    (net (code "74") (name "unconnected-(U1-VBAT-Pad1)") (class "Default")
      (node (ref "U1") (pin "1") (pinfunction "VBAT_1") (pintype "bidirectional"))
    )
    (net (code "75") (name "unconnected-(U2-GPIO4{slash}EXTPA-Pad11)") (class "Default")
      (node (ref "U2") (pin "11") (pinfunction "GPIO4/EXTPA_11") (pintype "bidirectional"))
    )
    (net (code "76") (name "unconnected-(U2-GPIO5{slash}EXTTXE{slash}SPIPOL-Pad10)") (class "Default")
      (node (ref "U2") (pin "10") (pinfunction "GPIO5/EXTTXE/SPIPOL_10") (pintype "bidirectional"))
    )
    (net (code "77") (name "unconnected-(U2-GPIO6{slash}EXTRXE{slash}SPIPHA-Pad9)") (class "Default")
      (node (ref "U2") (pin "9") (pinfunction "GPIO6/EXTRXE/SPIPHA_9") (pintype "bidirectional"))
    )
    (net (code "78") (name "unconnected-(U2-GPIO7-Pad4)") (class "Default")
      (node (ref "U2") (pin "4") (pinfunction "GPIO7_4") (pintype "input"))
    )
    (net (code "79") (name "unconnected-(U4-NC-Pad4)") (class "Default")
      (node (ref "U4") (pin "4") (pinfunction "NC_4") (pintype "power_in"))
    )
    (net (code "80") (name "unconnected-(U5-TD-Pad4)") (class "Default")
      (node (ref "U5") (pin "4") (pinfunction "TD_4") (pintype "bidirectional"))
    )
    (net (code "81") (name "unconnected-(U6-NC-Pad4)") (class "Default")
      (node (ref "U6") (pin "4") (pinfunction "NC_4") (pintype "power_in"))
    )
    (net (code "82") (name "unconnected-(U7-CTR#-Pad9)") (class "Default")
      (node (ref "U7") (pin "9") (pinfunction "CTR#_9") (pintype "passive"))
    )
    (net (code "83") (name "unconnected-(U7-DCD#-Pad12)") (class "Default")
      (node (ref "U7") (pin "12") (pinfunction "DCD#_12") (pintype "passive"))
    )
    (net (code "84") (name "unconnected-(U7-DSR#-Pad10)") (class "Default")
      (node (ref "U7") (pin "10") (pinfunction "DSR#_10") (pintype "passive"))
    )
    (net (code "85") (name "unconnected-(U7-DTR#-Pad13)") (class "Default")
      (node (ref "U7") (pin "13") (pinfunction "DTR#_13") (pintype "passive"))
    )
    (net (code "86") (name "unconnected-(U7-NC-Pad7)") (class "Default")
      (node (ref "U7") (pin "7") (pinfunction "NC_7") (pintype "passive"))
    )
    (net (code "87") (name "unconnected-(U7-NC-Pad8)") (class "Default")
      (node (ref "U7") (pin "8") (pinfunction "NC_8") (pintype "passive"))
    )
    (net (code "88") (name "unconnected-(U7-RI#-Pad11)") (class "Default")
      (node (ref "U7") (pin "11") (pinfunction "RI#_11") (pintype "passive"))
    )
    (net (code "89") (name "unconnected-(U7-RS232-Pad15)") (class "Default")
      (node (ref "U7") (pin "15") (pinfunction "RS232_15") (pintype "passive"))
    )
    (net (code "90") (name "unconnected-(U7-RTS#-Pad14)") (class "Default")
      (node (ref "U7") (pin "14") (pinfunction "RTS#_14") (pintype "passive"))
    )
    (net (code "91") (name "unconnected-(USB1-ID-Pad4)") (class "Default")
      (node (ref "USB1") (pin "4") (pinfunction "ID_4") (pintype "passive"))
    )
  )
)
